# AC_Project_thru_hole_V_1_02.net
KiCad netlist of a schematic drawn in EAGLE
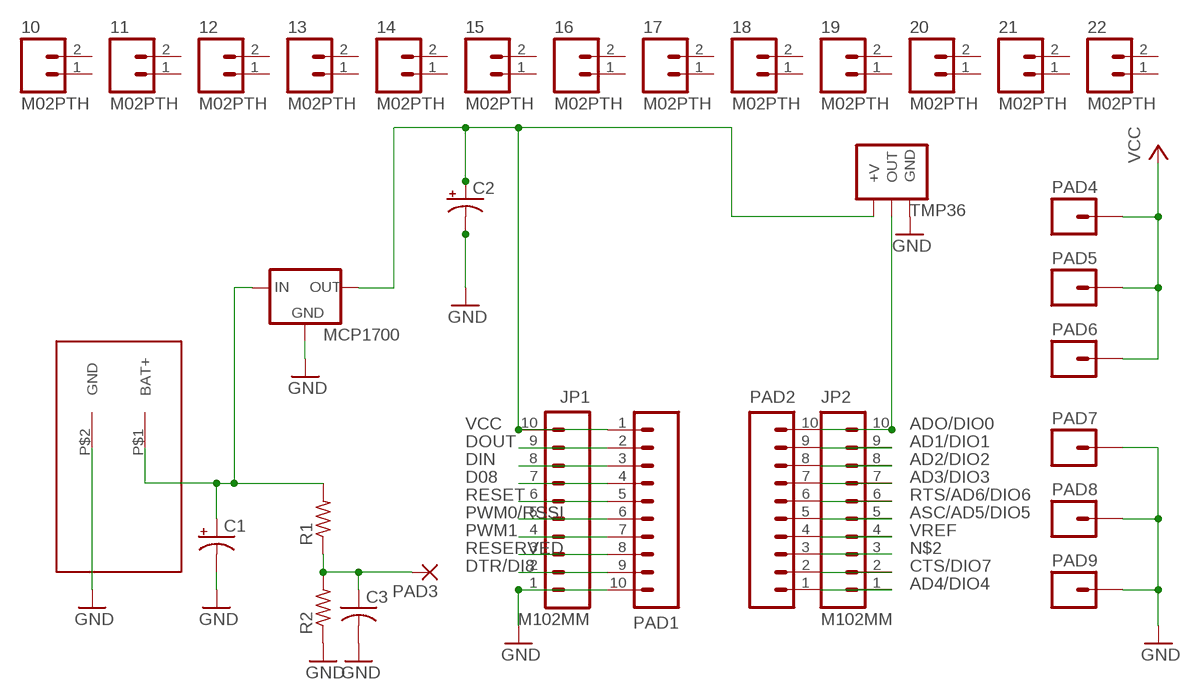
[diagram p0: schematic, sheet 1]

(export (version "E")
  (design (tool "Eeschema 10.0.6"))
  (components
    (comp (ref "10")
      (value "M02PTH")
      (footprint "eagle-import:1X02")
      (libsource (lib "eagle-import") (part "M02PTH"))
    )
    (comp (ref "11")
      (value "M02PTH")
      (footprint "eagle-import:1X02")
      (libsource (lib "eagle-import") (part "M02PTH"))
    )
    (comp (ref "12")
      (value "M02PTH")
      (footprint "eagle-import:1X02")
      (libsource (lib "eagle-import") (part "M02PTH"))
    )
    (comp (ref "13")
      (value "M02PTH")
      (footprint "eagle-import:1X02")
      (libsource (lib "eagle-import") (part "M02PTH"))
    )
    (comp (ref "14")
      (value "M02PTH")
      (footprint "eagle-import:1X02")
      (libsource (lib "eagle-import") (part "M02PTH"))
    )
    (comp (ref "15")
      (value "M02PTH")
      (footprint "eagle-import:1X02")
      (libsource (lib "eagle-import") (part "M02PTH"))
    )
    (comp (ref "16")
      (value "M02PTH")
      (footprint "eagle-import:1X02")
      (libsource (lib "eagle-import") (part "M02PTH"))
    )
    (comp (ref "17")
      (value "M02PTH")
      (footprint "eagle-import:1X02")
      (libsource (lib "eagle-import") (part "M02PTH"))
    )
    (comp (ref "18")
      (value "M02PTH")
      (footprint "eagle-import:1X02")
      (libsource (lib "eagle-import") (part "M02PTH"))
    )
    (comp (ref "19")
      (value "M02PTH")
      (footprint "eagle-import:1X02")
      (libsource (lib "eagle-import") (part "M02PTH"))
    )
    (comp (ref "20")
      (value "M02PTH")
      (footprint "eagle-import:1X02")
      (libsource (lib "eagle-import") (part "M02PTH"))
    )
    (comp (ref "21")
      (value "M02PTH")
      (footprint "eagle-import:1X02")
      (libsource (lib "eagle-import") (part "M02PTH"))
    )
    (comp (ref "22")
      (value "M02PTH")
      (footprint "eagle-import:1X02")
      (libsource (lib "eagle-import") (part "M02PTH"))
    )
    (comp (ref "C1")
      (value "CPOL-USE1.8-4")
      (footprint "eagle-import:E1,8-4")
      (libsource (lib "eagle-import") (part "CPOL-USE1.8-4"))
    )
    (comp (ref "C2")
      (value "CPOL-USE1.8-4")
      (footprint "eagle-import:E1,8-4")
      (libsource (lib "eagle-import") (part "CPOL-USE1.8-4"))
    )
    (comp (ref "C3")
      (value "C-US050-030X075")
      (footprint "eagle-import:C050-030X075")
      (libsource (lib "eagle-import") (part "C-US050-030X075"))
    )
    (comp (ref "JP1")
      (value "M102MM")
      (footprint "eagle-import:1X10-2MM")
      (libsource (lib "eagle-import") (part "M102MM"))
    )
    (comp (ref "JP2")
      (value "M102MM")
      (footprint "eagle-import:1X10-2MM")
      (libsource (lib "eagle-import") (part "M102MM"))
    )
    (comp (ref "MCP1700")
      (value "MCP1700INLINE")
      (footprint "eagle-import:TO92-INLINE")
      (libsource (lib "eagle-import") (part "MCP1700INLINE"))
    )
    (comp (ref "PAD1")
      (value "M10\"")
      (footprint "eagle-import:1X10")
      (libsource (lib "eagle-import") (part "M10{dblquote}"))
    )
    (comp (ref "PAD2")
      (value "M10\"")
      (footprint "eagle-import:1X10")
      (libsource (lib "eagle-import") (part "M10{dblquote}"))
    )
    (comp (ref "PAD3")
      (value "1,6/0,8")
      (footprint "eagle-import:1,6_0,8")
      (libsource (lib "eagle-import") (part "1,6/0,8"))
    )
    (comp (ref "PAD4")
      (value "M01PTH")
      (footprint "eagle-import:1X01")
      (libsource (lib "eagle-import") (part "M01PTH"))
    )
    (comp (ref "PAD5")
      (value "M01PTH")
      (footprint "eagle-import:1X01")
      (libsource (lib "eagle-import") (part "M01PTH"))
    )
    (comp (ref "PAD6")
      (value "M01PTH")
      (footprint "eagle-import:1X01")
      (libsource (lib "eagle-import") (part "M01PTH"))
    )
    (comp (ref "PAD7")
      (value "M01PTH")
      (footprint "eagle-import:1X01")
      (libsource (lib "eagle-import") (part "M01PTH"))
    )
    (comp (ref "PAD8")
      (value "M01PTH")
      (footprint "eagle-import:1X01")
      (libsource (lib "eagle-import") (part "M01PTH"))
    )
    (comp (ref "PAD9")
      (value "M01PTH")
      (footprint "eagle-import:1X01")
      (libsource (lib "eagle-import") (part "M01PTH"))
    )
    (comp (ref "R1")
      (value "R-US_0207/10")
      (footprint "eagle-import:0207_10")
      (libsource (lib "eagle-import") (part "R-US_0207/10"))
    )
    (comp (ref "R2")
      (value "R-US_0207/10")
      (footprint "eagle-import:0207_10")
      (libsource (lib "eagle-import") (part "R-US_0207/10"))
    )
    (comp (ref "TMP36")
      (value "TMP36INLINE")
      (footprint "eagle-import:TO92-INLINE")
      (libsource (lib "eagle-import") (part "TMP36INLINE"))
    )
    (comp (ref "U$2")
      (value "AAA_3X_HOLDERAAA_3X_HOLDER_THROUGH_HOLE")
      (footprint "eagle-import:AAA_3X_HOLDER")
      (libsource (lib "eagle-import") (part "AAA_3X_HOLDERAAA_3X_HOLDER_THROUGH_HOLE"))
    )
  )
  (nets
    (net (code "1") (name "/AD1{slash}DIO1") (class "Default")
      (node (ref "JP2") (pin "9") (pinfunction "9_9") (pintype "passive"))
      (node (ref "PAD2") (pin "9") (pinfunction "9_9") (pintype "passive"))
    )
    (net (code "2") (name "/AD2{slash}DIO2") (class "Default")
      (node (ref "JP2") (pin "8") (pinfunction "8_8") (pintype "passive"))
      (node (ref "PAD2") (pin "8") (pinfunction "8_8") (pintype "passive"))
    )
    (net (code "3") (name "/AD3{slash}DIO3") (class "Default")
      (node (ref "JP2") (pin "7") (pinfunction "7_7") (pintype "passive"))
      (node (ref "PAD2") (pin "7") (pinfunction "7_7") (pintype "passive"))
    )
    (net (code "4") (name "/AD4{slash}DIO4") (class "Default")
      (node (ref "JP2") (pin "1") (pinfunction "1_1") (pintype "passive"))
      (node (ref "PAD2") (pin "1") (pinfunction "1_1") (pintype "passive"))
    )
    (net (code "5") (name "/ADO{slash}DIO0") (class "Default")
      (node (ref "JP2") (pin "10") (pinfunction "10_10") (pintype "passive"))
      (node (ref "PAD2") (pin "10") (pinfunction "10_10") (pintype "passive"))
      (node (ref "TMP36") (pin "2") (pinfunction "OUT_2") (pintype "output"))
    )
    (net (code "6") (name "/ASC{slash}AD5{slash}DIO5") (class "Default")
      (node (ref "JP2") (pin "5") (pinfunction "5_5") (pintype "passive"))
      (node (ref "PAD2") (pin "5") (pinfunction "5_5") (pintype "passive"))
    )
    (net (code "7") (name "/CTS{slash}DIO7") (class "Default")
      (node (ref "JP2") (pin "2") (pinfunction "2_2") (pintype "passive"))
      (node (ref "PAD2") (pin "2") (pinfunction "2_2") (pintype "passive"))
    )
    (net (code "8") (name "/D08") (class "Default")
      (node (ref "JP1") (pin "7") (pinfunction "7_7") (pintype "passive"))
      (node (ref "PAD1") (pin "4") (pinfunction "4_4") (pintype "passive"))
    )
    (net (code "9") (name "/DIN") (class "Default")
      (node (ref "JP1") (pin "8") (pinfunction "8_8") (pintype "passive"))
      (node (ref "PAD1") (pin "3") (pinfunction "3_3") (pintype "passive"))
    )
    (net (code "10") (name "/DOUT") (class "Default")
      (node (ref "JP1") (pin "9") (pinfunction "9_9") (pintype "passive"))
      (node (ref "PAD1") (pin "2") (pinfunction "2_2") (pintype "passive"))
    )
    (net (code "11") (name "/DTR{slash}DI8") (class "Default")
      (node (ref "JP1") (pin "2") (pinfunction "2_2") (pintype "passive"))
      (node (ref "PAD1") (pin "9") (pinfunction "9_9") (pintype "passive"))
    )
    (net (code "12") (name "/N$2") (class "Default")
      (node (ref "JP2") (pin "3") (pinfunction "3_3") (pintype "passive"))
      (node (ref "PAD2") (pin "3") (pinfunction "3_3") (pintype "passive"))
    )
    (net (code "13") (name "/PWM0{slash}RSSI") (class "Default")
      (node (ref "JP1") (pin "5") (pinfunction "5_5") (pintype "passive"))
      (node (ref "PAD1") (pin "6") (pinfunction "6_6") (pintype "passive"))
    )
    (net (code "14") (name "/PWM1") (class "Default")
      (node (ref "JP1") (pin "4") (pinfunction "4_4") (pintype "passive"))
      (node (ref "PAD1") (pin "7") (pinfunction "7_7") (pintype "passive"))
    )
    (net (code "15") (name "/RESERVED") (class "Default")
      (node (ref "JP1") (pin "3") (pinfunction "3_3") (pintype "passive"))
      (node (ref "PAD1") (pin "8") (pinfunction "8_8") (pintype "passive"))
    )
    (net (code "16") (name "/RESET") (class "Default")
      (node (ref "JP1") (pin "6") (pinfunction "6_6") (pintype "passive"))
      (node (ref "PAD1") (pin "5") (pinfunction "5_5") (pintype "passive"))
    )
    (net (code "17") (name "/RTS{slash}AD6{slash}DIO6") (class "Default")
      (node (ref "JP2") (pin "6") (pinfunction "6_6") (pintype "passive"))
      (node (ref "PAD2") (pin "6") (pinfunction "6_6") (pintype "passive"))
    )
    (net (code "18") (name "/VREF") (class "Default")
      (node (ref "JP2") (pin "4") (pinfunction "4_4") (pintype "passive"))
      (node (ref "PAD2") (pin "4") (pinfunction "4_4") (pintype "passive"))
    )
    (net (code "19") (name "GND") (class "Default")
      (node (ref "C1") (pin "-") (pinfunction "-_-") (pintype "passive"))
      (node (ref "C2") (pin "-") (pinfunction "-_-") (pintype "passive"))
      (node (ref "C3") (pin "2") (pinfunction "2_2") (pintype "passive"))
      (node (ref "JP1") (pin "1") (pinfunction "1_1") (pintype "passive"))
      (node (ref "MCP1700") (pin "1") (pinfunction "GND_1") (pintype "input"))
      (node (ref "PAD1") (pin "10") (pinfunction "10_10") (pintype "passive"))
      (node (ref "PAD7") (pin "1") (pinfunction "1_1") (pintype "passive"))
      (node (ref "PAD8") (pin "1") (pinfunction "1_1") (pintype "passive"))
      (node (ref "PAD9") (pin "1") (pinfunction "1_1") (pintype "passive"))
      (node (ref "R2") (pin "1") (pinfunction "1_1") (pintype "passive"))
      (node (ref "TMP36") (pin "3") (pinfunction "GND_3") (pintype "input"))
      (node (ref "U$2") (pin "P$2") (pinfunction "GND_P$2") (pintype "bidirectional"))
    )
    (net (code "20") (name "Net-(MCP1700-IN)") (class "Default")
      (node (ref "C1") (pin "+") (pinfunction "+_+") (pintype "passive"))
      (node (ref "MCP1700") (pin "2") (pinfunction "IN_2") (pintype "input"))
      (node (ref "R1") (pin "2") (pinfunction "2_2") (pintype "passive"))
      (node (ref "U$2") (pin "P$1") (pinfunction "BAT+_P$1") (pintype "bidirectional"))
    )
    (net (code "21") (name "Net-(PAD3-P)") (class "Default")
      (node (ref "C3") (pin "1") (pinfunction "1_1") (pintype "passive"))
      (node (ref "PAD3") (pin "1") (pinfunction "P_1") (pintype "passive"))
      (node (ref "R1") (pin "1") (pinfunction "1_1") (pintype "passive"))
      (node (ref "R2") (pin "2") (pinfunction "2_2") (pintype "passive"))
    )
    (net (code "22") (name "VCC") (class "Default")
      (node (ref "C2") (pin "+") (pinfunction "+_+") (pintype "passive"))
      (node (ref "JP1") (pin "10") (pinfunction "10_10") (pintype "passive"))
      (node (ref "MCP1700") (pin "3") (pinfunction "OUT_3") (pintype "passive"))
      (node (ref "PAD1") (pin "1") (pinfunction "1_1") (pintype "passive"))
      (node (ref "PAD4") (pin "1") (pinfunction "1_1") (pintype "passive"))
      (node (ref "PAD5") (pin "1") (pinfunction "1_1") (pintype "passive"))
      (node (ref "PAD6") (pin "1") (pinfunction "1_1") (pintype "passive"))
      (node (ref "TMP36") (pin "1") (pinfunction "+V_1") (pintype "input"))
    )
    (net (code "23") (name "unconnected-(10-Pad1)") (class "Default")
      (node (ref "10") (pin "1") (pinfunction "1_1") (pintype "passive"))
    )
    (net (code "24") (name "unconnected-(10-Pad2)") (class "Default")
      (node (ref "10") (pin "2") (pinfunction "2_2") (pintype "passive"))
    )
    (net (code "25") (name "unconnected-(11-Pad1)") (class "Default")
      (node (ref "11") (pin "1") (pinfunction "1_1") (pintype "passive"))
    )
    (net (code "26") (name "unconnected-(11-Pad2)") (class "Default")
      (node (ref "11") (pin "2") (pinfunction "2_2") (pintype "passive"))
    )
    (net (code "27") (name "unconnected-(12-Pad1)") (class "Default")
      (node (ref "12") (pin "1") (pinfunction "1_1") (pintype "passive"))
    )
    (net (code "28") (name "unconnected-(12-Pad2)") (class "Default")
      (node (ref "12") (pin "2") (pinfunction "2_2") (pintype "passive"))
    )
    (net (code "29") (name "unconnected-(13-Pad1)") (class "Default")
      (node (ref "13") (pin "1") (pinfunction "1_1") (pintype "passive"))
    )
    (net (code "30") (name "unconnected-(13-Pad2)") (class "Default")
      (node (ref "13") (pin "2") (pinfunction "2_2") (pintype "passive"))
    )
    (net (code "31") (name "unconnected-(14-Pad1)") (class "Default")
      (node (ref "14") (pin "1") (pinfunction "1_1") (pintype "passive"))
    )
    (net (code "32") (name "unconnected-(14-Pad2)") (class "Default")
      (node (ref "14") (pin "2") (pinfunction "2_2") (pintype "passive"))
    )
    (net (code "33") (name "unconnected-(15-Pad1)") (class "Default")
      (node (ref "15") (pin "1") (pinfunction "1_1") (pintype "passive"))
    )
    (net (code "34") (name "unconnected-(15-Pad2)") (class "Default")
      (node (ref "15") (pin "2") (pinfunction "2_2") (pintype "passive"))
    )
    (net (code "35") (name "unconnected-(16-Pad1)") (class "Default")
      (node (ref "16") (pin "1") (pinfunction "1_1") (pintype "passive"))
    )
    (net (code "36") (name "unconnected-(16-Pad2)") (class "Default")
      (node (ref "16") (pin "2") (pinfunction "2_2") (pintype "passive"))
    )
    (net (code "37") (name "unconnected-(17-Pad1)") (class "Default")
      (node (ref "17") (pin "1") (pinfunction "1_1") (pintype "passive"))
    )
    (net (code "38") (name "unconnected-(17-Pad2)") (class "Default")
      (node (ref "17") (pin "2") (pinfunction "2_2") (pintype "passive"))
    )
    (net (code "39") (name "unconnected-(18-Pad1)") (class "Default")
      (node (ref "18") (pin "1") (pinfunction "1_1") (pintype "passive"))
    )
    (net (code "40") (name "unconnected-(18-Pad2)") (class "Default")
      (node (ref "18") (pin "2") (pinfunction "2_2") (pintype "passive"))
    )
    (net (code "41") (name "unconnected-(19-Pad1)") (class "Default")
      (node (ref "19") (pin "1") (pinfunction "1_1") (pintype "passive"))
    )
    (net (code "42") (name "unconnected-(19-Pad2)") (class "Default")
      (node (ref "19") (pin "2") (pinfunction "2_2") (pintype "passive"))
    )
    (net (code "43") (name "unconnected-(20-Pad1)") (class "Default")
      (node (ref "20") (pin "1") (pinfunction "1_1") (pintype "passive"))
    )
    (net (code "44") (name "unconnected-(20-Pad2)") (class "Default")
      (node (ref "20") (pin "2") (pinfunction "2_2") (pintype "passive"))
    )
    (net (code "45") (name "unconnected-(21-Pad1)") (class "Default")
      (node (ref "21") (pin "1") (pinfunction "1_1") (pintype "passive"))
    )
    (net (code "46") (name "unconnected-(21-Pad2)") (class "Default")
      (node (ref "21") (pin "2") (pinfunction "2_2") (pintype "passive"))
    )
    (net (code "47") (name "unconnected-(22-Pad1)") (class "Default")
      (node (ref "22") (pin "1") (pinfunction "1_1") (pintype "passive"))
    )
    (net (code "48") (name "unconnected-(22-Pad2)") (class "Default")
      (node (ref "22") (pin "2") (pinfunction "2_2") (pintype "passive"))
    )
  )
)
